# PLACA3P.net
KiCad netlist of a schematic drawn in EAGLE
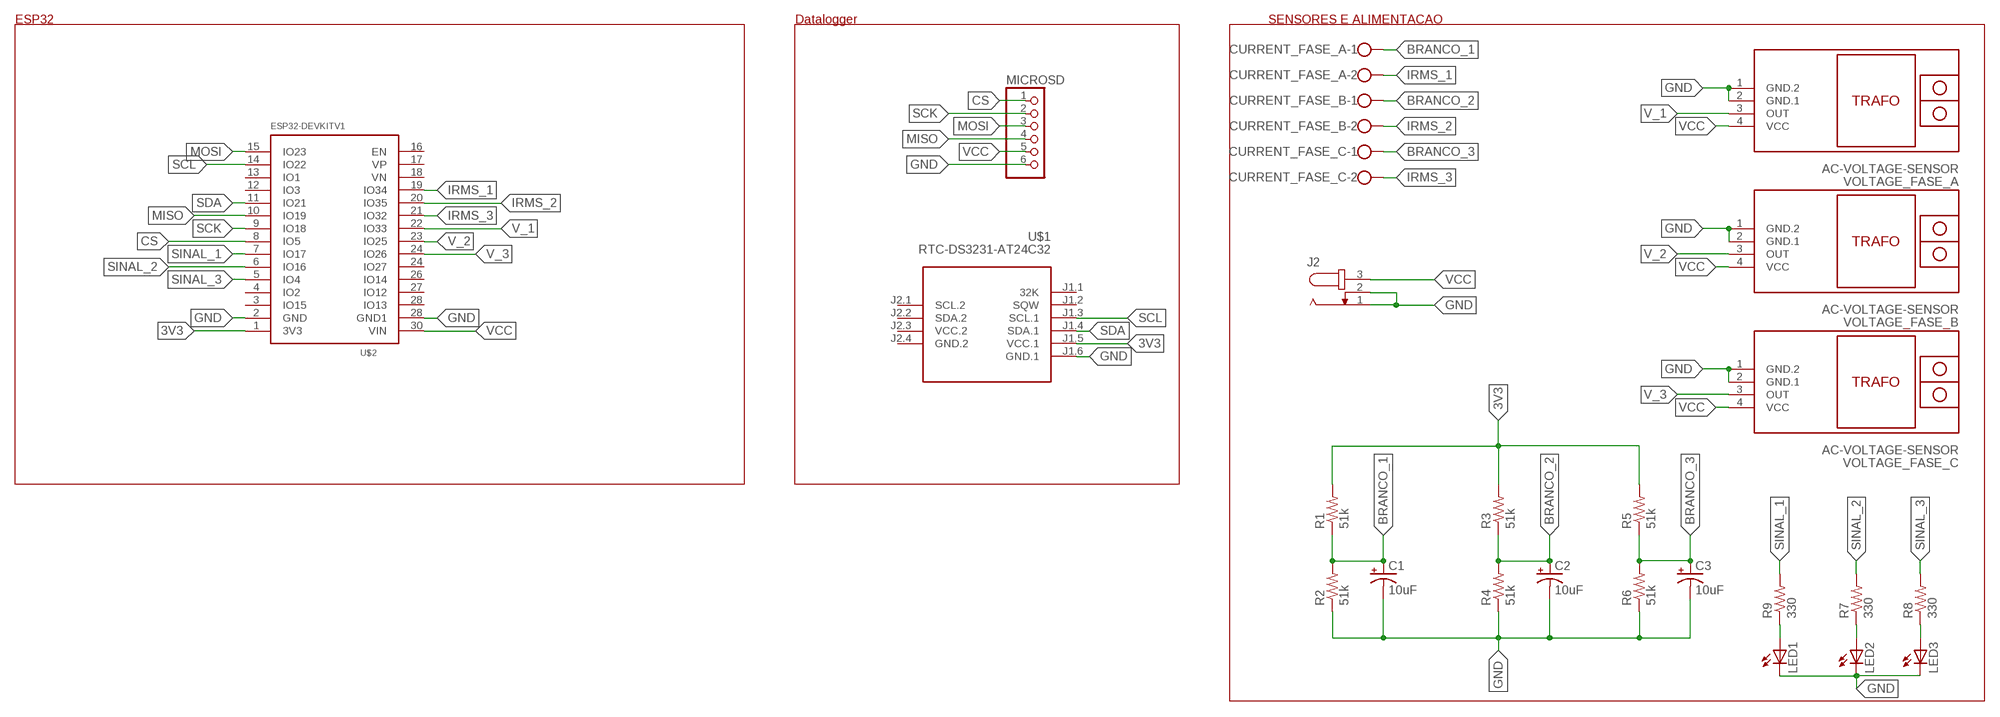
[diagram p0: schematic, sheet 1]

(export (version "E")
  (design (tool "Eeschema 10.0.6"))
  (components
    (comp (ref "C1")
      (value "10uF")
      (footprint "eagle-import:E2-4")
      (libsource (lib "eagle-import") (part "CPOL-USE2-4"))
    )
    (comp (ref "C2")
      (value "10uF")
      (footprint "eagle-import:E2-4")
      (libsource (lib "eagle-import") (part "CPOL-USE2-4"))
    )
    (comp (ref "C3")
      (value "10uF")
      (footprint "eagle-import:E2-4")
      (libsource (lib "eagle-import") (part "CPOL-USE2-4"))
    )
    (comp (ref "CURRENT_FASE_A")
      (value "W237-102")
      (footprint "eagle-import:W237-102")
      (fields (field (name "MPN") "237-102"))
      (libsource (lib "eagle-import") (part "W237-102"))
    )
    (comp (ref "CURRENT_FASE_B")
      (value "W237-102")
      (footprint "eagle-import:W237-102")
      (fields (field (name "MPN") "237-102"))
      (libsource (lib "eagle-import") (part "W237-102"))
    )
    (comp (ref "CURRENT_FASE_C")
      (value "W237-102")
      (footprint "eagle-import:W237-102")
      (fields (field (name "MPN") "237-102"))
      (libsource (lib "eagle-import") (part "W237-102"))
    )
    (comp (ref "J2")
      (value "JACK-PLUG1")
      (footprint "eagle-import:SPC4078")
      (libsource (lib "eagle-import") (part "JACK-PLUG1"))
    )
    (comp (ref "LED1")
      (value "LED5MM")
      (footprint "eagle-import:LED5MM")
      (libsource (lib "eagle-import") (part "LED5MM"))
    )
    (comp (ref "LED2")
      (value "LED5MM")
      (footprint "eagle-import:LED5MM")
      (libsource (lib "eagle-import") (part "LED5MM"))
    )
    (comp (ref "LED3")
      (value "LED5MM")
      (footprint "eagle-import:LED5MM")
      (libsource (lib "eagle-import") (part "LED5MM"))
    )
    (comp (ref "MICROSD")
      (value "PINHD-1X6B")
      (footprint "eagle-import:1X06-BIG")
      (libsource (lib "eagle-import") (part "PINHD-1X6B"))
    )
    (comp (ref "R1")
      (value "51k")
      (footprint "eagle-import:0207_12")
      (libsource (lib "eagle-import") (part "R-US_0207/12"))
    )
    (comp (ref "R2")
      (value "51k")
      (footprint "eagle-import:0207_12")
      (libsource (lib "eagle-import") (part "R-US_0207/12"))
    )
    (comp (ref "R3")
      (value "51k")
      (footprint "eagle-import:0207_12")
      (libsource (lib "eagle-import") (part "R-US_0207/12"))
    )
    (comp (ref "R4")
      (value "51k")
      (footprint "eagle-import:0207_12")
      (libsource (lib "eagle-import") (part "R-US_0207/12"))
    )
    (comp (ref "R5")
      (value "51k")
      (footprint "eagle-import:0207_12")
      (libsource (lib "eagle-import") (part "R-US_0207/12"))
    )
    (comp (ref "R6")
      (value "51k")
      (footprint "eagle-import:0207_12")
      (libsource (lib "eagle-import") (part "R-US_0207/12"))
    )
    (comp (ref "R7")
      (value "330")
      (footprint "eagle-import:0207_12")
      (libsource (lib "eagle-import") (part "R-US_0207/12"))
    )
    (comp (ref "R8")
      (value "330")
      (footprint "eagle-import:0207_12")
      (libsource (lib "eagle-import") (part "R-US_0207/12"))
    )
    (comp (ref "R9")
      (value "330")
      (footprint "eagle-import:0207_12")
      (libsource (lib "eagle-import") (part "R-US_0207/12"))
    )
    (comp (ref "U$1")
      (value "RTC-DS3231-AT24C32")
      (footprint "eagle-import:RTC-DS3231-AT24C32")
      (libsource (lib "eagle-import") (part "RTC-DS3231-AT24C32"))
    )
    (comp (ref "U$2")
      (value "ESP32DEVKITV1")
      (footprint "eagle-import:ESP32-DEVKITV1")
      (libsource (lib "eagle-import") (part "ESP32DEVKITV1"))
    )
    (comp (ref "VOLTAGE_FASE_A")
      (value "AC-VOLTAGE-SENSOR")
      (footprint "eagle-import:AC-VOLTAGE-SENSOR")
      (libsource (lib "eagle-import") (part "AC-VOLTAGE-SENSOR"))
    )
    (comp (ref "VOLTAGE_FASE_B")
      (value "AC-VOLTAGE-SENSOR")
      (footprint "eagle-import:AC-VOLTAGE-SENSOR")
      (libsource (lib "eagle-import") (part "AC-VOLTAGE-SENSOR"))
    )
    (comp (ref "VOLTAGE_FASE_C")
      (value "AC-VOLTAGE-SENSOR")
      (footprint "eagle-import:AC-VOLTAGE-SENSOR")
      (libsource (lib "eagle-import") (part "AC-VOLTAGE-SENSOR"))
    )
  )
  (nets
    (net (code "1") (name "/GND.2") (class "Default")
      (node (ref "U$1") (pin "J2.4") (pinfunction "GND.2_J2.4") (pintype "power_in"))
    )
    (net (code "2") (name "/VCC.2") (class "Default")
      (node (ref "U$1") (pin "J2.3") (pinfunction "VCC.2_J2.3") (pintype "power_in"))
    )
    (net (code "3") (name "3V3") (class "Default")
      (node (ref "R1") (pin "2") (pinfunction "2_2") (pintype "passive"))
      (node (ref "R3") (pin "2") (pinfunction "2_2") (pintype "passive"))
      (node (ref "R5") (pin "2") (pinfunction "2_2") (pintype "passive"))
      (node (ref "U$1") (pin "J1.5") (pinfunction "VCC.1_J1.5") (pintype "power_in"))
      (node (ref "U$2") (pin "1") (pinfunction "3V3_1") (pintype "bidirectional"))
    )
    (net (code "4") (name "BRANCO_1") (class "Default")
      (node (ref "C1") (pin "+") (pinfunction "+_+") (pintype "passive"))
      (node (ref "CURRENT_FASE_A") (pin "1") (pinfunction "KL_1") (pintype "passive"))
      (node (ref "R1") (pin "1") (pinfunction "1_1") (pintype "passive"))
      (node (ref "R2") (pin "2") (pinfunction "2_2") (pintype "passive"))
    )
    (net (code "5") (name "BRANCO_2") (class "Default")
      (node (ref "C2") (pin "+") (pinfunction "+_+") (pintype "passive"))
      (node (ref "CURRENT_FASE_B") (pin "1") (pinfunction "KL_1") (pintype "passive"))
      (node (ref "R3") (pin "1") (pinfunction "1_1") (pintype "passive"))
      (node (ref "R4") (pin "2") (pinfunction "2_2") (pintype "passive"))
    )
    (net (code "6") (name "BRANCO_3") (class "Default")
      (node (ref "C3") (pin "+") (pinfunction "+_+") (pintype "passive"))
      (node (ref "CURRENT_FASE_C") (pin "1") (pinfunction "KL_1") (pintype "passive"))
      (node (ref "R5") (pin "1") (pinfunction "1_1") (pintype "passive"))
      (node (ref "R6") (pin "2") (pinfunction "2_2") (pintype "passive"))
    )
    (net (code "7") (name "CS") (class "Default")
      (node (ref "MICROSD") (pin "1") (pinfunction "1_1") (pintype "passive"))
      (node (ref "U$2") (pin "8") (pinfunction "IO5_8") (pintype "bidirectional"))
    )
    (net (code "8") (name "GND") (class "Default")
      (node (ref "C1") (pin "-") (pinfunction "-_-") (pintype "passive"))
      (node (ref "C2") (pin "-") (pinfunction "-_-") (pintype "passive"))
      (node (ref "C3") (pin "-") (pinfunction "-_-") (pintype "passive"))
      (node (ref "J2") (pin "1") (pinfunction "1_1") (pintype "passive"))
      (node (ref "J2") (pin "2") (pinfunction "2_2") (pintype "passive"))
      (node (ref "LED1") (pin "K") (pinfunction "C_K") (pintype "passive"))
      (node (ref "LED2") (pin "K") (pinfunction "C_K") (pintype "passive"))
      (node (ref "LED3") (pin "K") (pinfunction "C_K") (pintype "passive"))
      (node (ref "MICROSD") (pin "6") (pinfunction "6_6") (pintype "passive"))
      (node (ref "R2") (pin "1") (pinfunction "1_1") (pintype "passive"))
      (node (ref "R4") (pin "1") (pinfunction "1_1") (pintype "passive"))
      (node (ref "R6") (pin "1") (pinfunction "1_1") (pintype "passive"))
      (node (ref "U$1") (pin "J1.6") (pinfunction "GND.1_J1.6") (pintype "power_in"))
      (node (ref "U$2") (pin "2") (pinfunction "GND_2") (pintype "bidirectional"))
      (node (ref "U$2") (pin "28") (pinfunction "GND1_28") (pintype "bidirectional"))
      (node (ref "VOLTAGE_FASE_A") (pin "1") (pinfunction "GND.2_1") (pintype "power_in"))
      (node (ref "VOLTAGE_FASE_A") (pin "2") (pinfunction "GND.1_2") (pintype "power_in"))
      (node (ref "VOLTAGE_FASE_B") (pin "1") (pinfunction "GND.2_1") (pintype "power_in"))
      (node (ref "VOLTAGE_FASE_B") (pin "2") (pinfunction "GND.1_2") (pintype "power_in"))
      (node (ref "VOLTAGE_FASE_C") (pin "1") (pinfunction "GND.2_1") (pintype "power_in"))
      (node (ref "VOLTAGE_FASE_C") (pin "2") (pinfunction "GND.1_2") (pintype "power_in"))
    )
    (net (code "9") (name "IRMS_1") (class "Default")
      (node (ref "CURRENT_FASE_A") (pin "2") (pinfunction "KL_2") (pintype "passive"))
      (node (ref "U$2") (pin "19") (pinfunction "IO34_19") (pintype "bidirectional"))
    )
    (net (code "10") (name "IRMS_2") (class "Default")
      (node (ref "CURRENT_FASE_B") (pin "2") (pinfunction "KL_2") (pintype "passive"))
      (node (ref "U$2") (pin "20") (pinfunction "IO35_20") (pintype "bidirectional"))
    )
    (net (code "11") (name "IRMS_3") (class "Default")
      (node (ref "CURRENT_FASE_C") (pin "2") (pinfunction "KL_2") (pintype "passive"))
      (node (ref "U$2") (pin "21") (pinfunction "IO32_21") (pintype "bidirectional"))
    )
    (net (code "12") (name "MISO") (class "Default")
      (node (ref "MICROSD") (pin "4") (pinfunction "4_4") (pintype "passive"))
      (node (ref "U$2") (pin "10") (pinfunction "IO19_10") (pintype "bidirectional"))
    )
    (net (code "13") (name "MOSI") (class "Default")
      (node (ref "MICROSD") (pin "3") (pinfunction "3_3") (pintype "passive"))
      (node (ref "U$2") (pin "15") (pinfunction "IO23_15") (pintype "bidirectional"))
    )
    (net (code "14") (name "Net-(LED1-PadA)") (class "Default")
      (node (ref "LED1") (pin "A") (pinfunction "A_A") (pintype "passive"))
      (node (ref "R9") (pin "1") (pinfunction "1_1") (pintype "passive"))
    )
    (net (code "15") (name "Net-(LED2-PadA)") (class "Default")
      (node (ref "LED2") (pin "A") (pinfunction "A_A") (pintype "passive"))
      (node (ref "R7") (pin "1") (pinfunction "1_1") (pintype "passive"))
    )
    (net (code "16") (name "Net-(LED3-PadA)") (class "Default")
      (node (ref "LED3") (pin "A") (pinfunction "A_A") (pintype "passive"))
      (node (ref "R8") (pin "1") (pinfunction "1_1") (pintype "passive"))
    )
    (net (code "17") (name "SCK") (class "Default")
      (node (ref "MICROSD") (pin "2") (pinfunction "2_2") (pintype "passive"))
      (node (ref "U$2") (pin "9") (pinfunction "IO18_9") (pintype "bidirectional"))
    )
    (net (code "18") (name "SCL") (class "Default")
      (node (ref "U$1") (pin "J1.3") (pinfunction "SCL.1_J1.3") (pintype "bidirectional"))
      (node (ref "U$2") (pin "14") (pinfunction "IO22_14") (pintype "bidirectional"))
    )
    (net (code "19") (name "SDA") (class "Default")
      (node (ref "U$1") (pin "J1.4") (pinfunction "SDA.1_J1.4") (pintype "bidirectional"))
      (node (ref "U$2") (pin "11") (pinfunction "IO21_11") (pintype "bidirectional"))
    )
    (net (code "20") (name "SINAL_1") (class "Default")
      (node (ref "R9") (pin "2") (pinfunction "2_2") (pintype "passive"))
      (node (ref "U$2") (pin "7") (pinfunction "IO17_7") (pintype "bidirectional"))
    )
    (net (code "21") (name "SINAL_2") (class "Default")
      (node (ref "R7") (pin "2") (pinfunction "2_2") (pintype "passive"))
      (node (ref "U$2") (pin "6") (pinfunction "IO16_6") (pintype "bidirectional"))
    )
    (net (code "22") (name "SINAL_3") (class "Default")
      (node (ref "R8") (pin "2") (pinfunction "2_2") (pintype "passive"))
      (node (ref "U$2") (pin "5") (pinfunction "IO4_5") (pintype "bidirectional"))
    )
    (net (code "23") (name "VCC") (class "Default")
      (node (ref "J2") (pin "3") (pinfunction "3_3") (pintype "passive"))
      (node (ref "MICROSD") (pin "5") (pinfunction "5_5") (pintype "passive"))
      (node (ref "U$2") (pin "30") (pinfunction "VIN_30") (pintype "bidirectional"))
      (node (ref "VOLTAGE_FASE_A") (pin "4") (pinfunction "VCC_4") (pintype "power_in"))
      (node (ref "VOLTAGE_FASE_B") (pin "4") (pinfunction "VCC_4") (pintype "power_in"))
      (node (ref "VOLTAGE_FASE_C") (pin "4") (pinfunction "VCC_4") (pintype "power_in"))
    )
    (net (code "24") (name "V_1") (class "Default")
      (node (ref "U$2") (pin "22") (pinfunction "IO33_22") (pintype "bidirectional"))
      (node (ref "VOLTAGE_FASE_A") (pin "3") (pinfunction "OUT_3") (pintype "output"))
    )
    (net (code "25") (name "V_2") (class "Default")
      (node (ref "U$2") (pin "23") (pinfunction "IO25_23") (pintype "bidirectional"))
      (node (ref "VOLTAGE_FASE_B") (pin "3") (pinfunction "OUT_3") (pintype "output"))
    )
    (net (code "26") (name "V_3") (class "Default")
      (node (ref "U$2") (pin "24") (pinfunction "IO26_24") (pintype "bidirectional"))
      (node (ref "VOLTAGE_FASE_C") (pin "3") (pinfunction "OUT_3") (pintype "output"))
    )
    (net (code "27") (name "unconnected-(U$1-32K-PadJ1.1)") (class "Default")
      (node (ref "U$1") (pin "J1.1") (pinfunction "32K_J1.1") (pintype "bidirectional"))
    )
    (net (code "28") (name "unconnected-(U$1-SCL.2-PadJ2.1)") (class "Default")
      (node (ref "U$1") (pin "J2.1") (pinfunction "SCL.2_J2.1") (pintype "bidirectional"))
    )
    (net (code "29") (name "unconnected-(U$1-SDA.2-PadJ2.2)") (class "Default")
      (node (ref "U$1") (pin "J2.2") (pinfunction "SDA.2_J2.2") (pintype "bidirectional"))
    )
    (net (code "30") (name "unconnected-(U$1-SQW-PadJ1.2)") (class "Default")
      (node (ref "U$1") (pin "J1.2") (pinfunction "SQW_J1.2") (pintype "bidirectional"))
    )
    (net (code "31") (name "unconnected-(U$2-EN-Pad16)") (class "Default")
      (node (ref "U$2") (pin "16") (pinfunction "EN_16") (pintype "bidirectional"))
    )
    (net (code "32") (name "unconnected-(U$2-IO1-Pad13)") (class "Default")
      (node (ref "U$2") (pin "13") (pinfunction "IO1_13") (pintype "bidirectional"))
    )
    (net (code "33") (name "unconnected-(U$2-IO2-Pad4)") (class "Default")
      (node (ref "U$2") (pin "4") (pinfunction "IO2_4") (pintype "bidirectional"))
    )
    (net (code "34") (name "unconnected-(U$2-IO3-Pad12)") (class "Default")
      (node (ref "U$2") (pin "12") (pinfunction "IO3_12") (pintype "bidirectional"))
    )
    (net (code "35") (name "unconnected-(U$2-IO12-Pad27)") (class "Default")
      (node (ref "U$2") (pin "27") (pinfunction "IO12_27") (pintype "bidirectional"))
    )
    (net (code "36") (name "unconnected-(U$2-IO13-Pad28)") (class "Default")
      (node (ref "U$2") (pin "28") (pinfunction "IO13_28") (pintype "bidirectional"))
    )
    (net (code "37") (name "unconnected-(U$2-IO14-Pad26)") (class "Default")
      (node (ref "U$2") (pin "26") (pinfunction "IO14_26") (pintype "bidirectional"))
    )
    (net (code "38") (name "unconnected-(U$2-IO15-Pad3)") (class "Default")
      (node (ref "U$2") (pin "3") (pinfunction "IO15_3") (pintype "bidirectional"))
    )
    (net (code "39") (name "unconnected-(U$2-IO27-Pad24)") (class "Default")
      (node (ref "U$2") (pin "24") (pinfunction "IO27_24") (pintype "bidirectional"))
    )
    (net (code "40") (name "unconnected-(U$2-VN-Pad18)") (class "Default")
      (node (ref "U$2") (pin "18") (pinfunction "VN_18") (pintype "bidirectional"))
    )
    (net (code "41") (name "unconnected-(U$2-VP-Pad17)") (class "Default")
      (node (ref "U$2") (pin "17") (pinfunction "VP_17") (pintype "bidirectional"))
    )
  )
)
